# Sheet1.net
KiCad netlist of a schematic drawn in Altium Designer
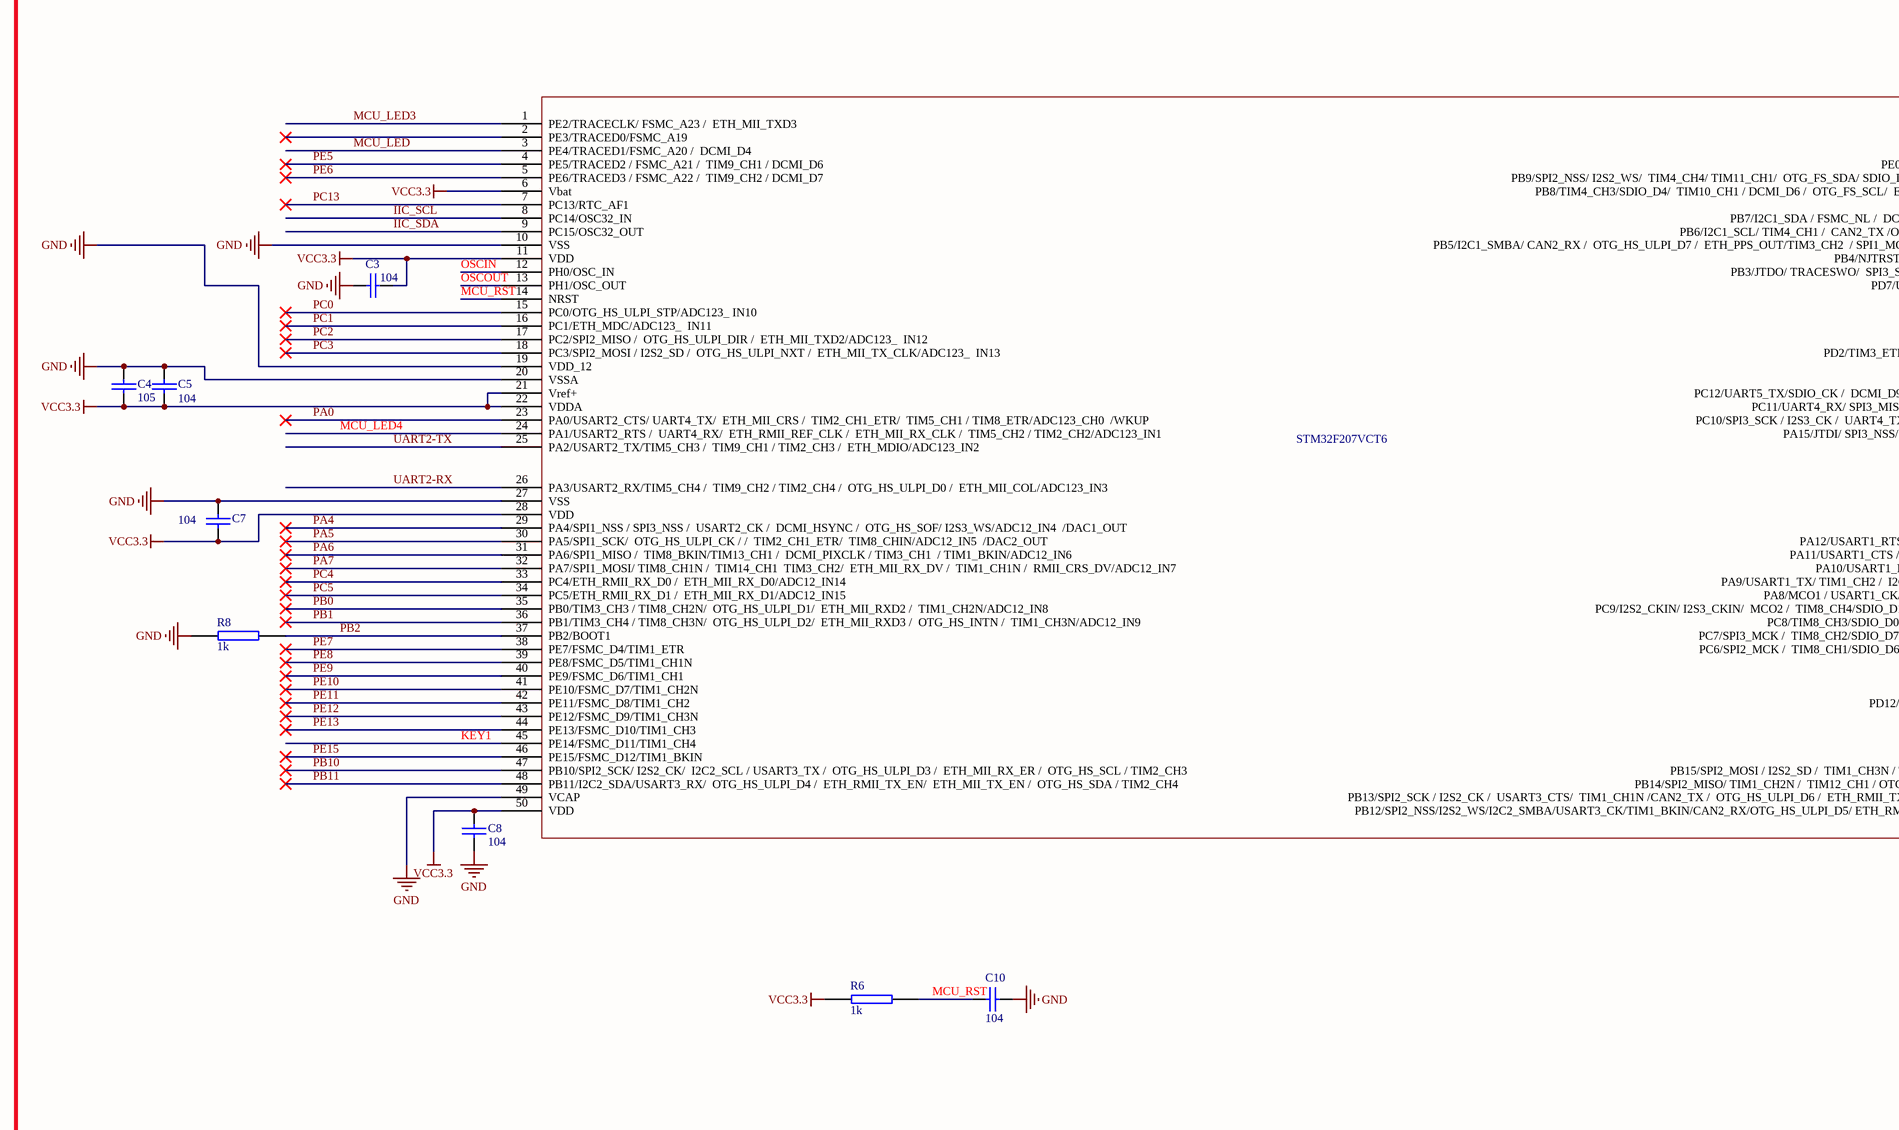
[diagram p0: Sheet1.SchDoc, top left]
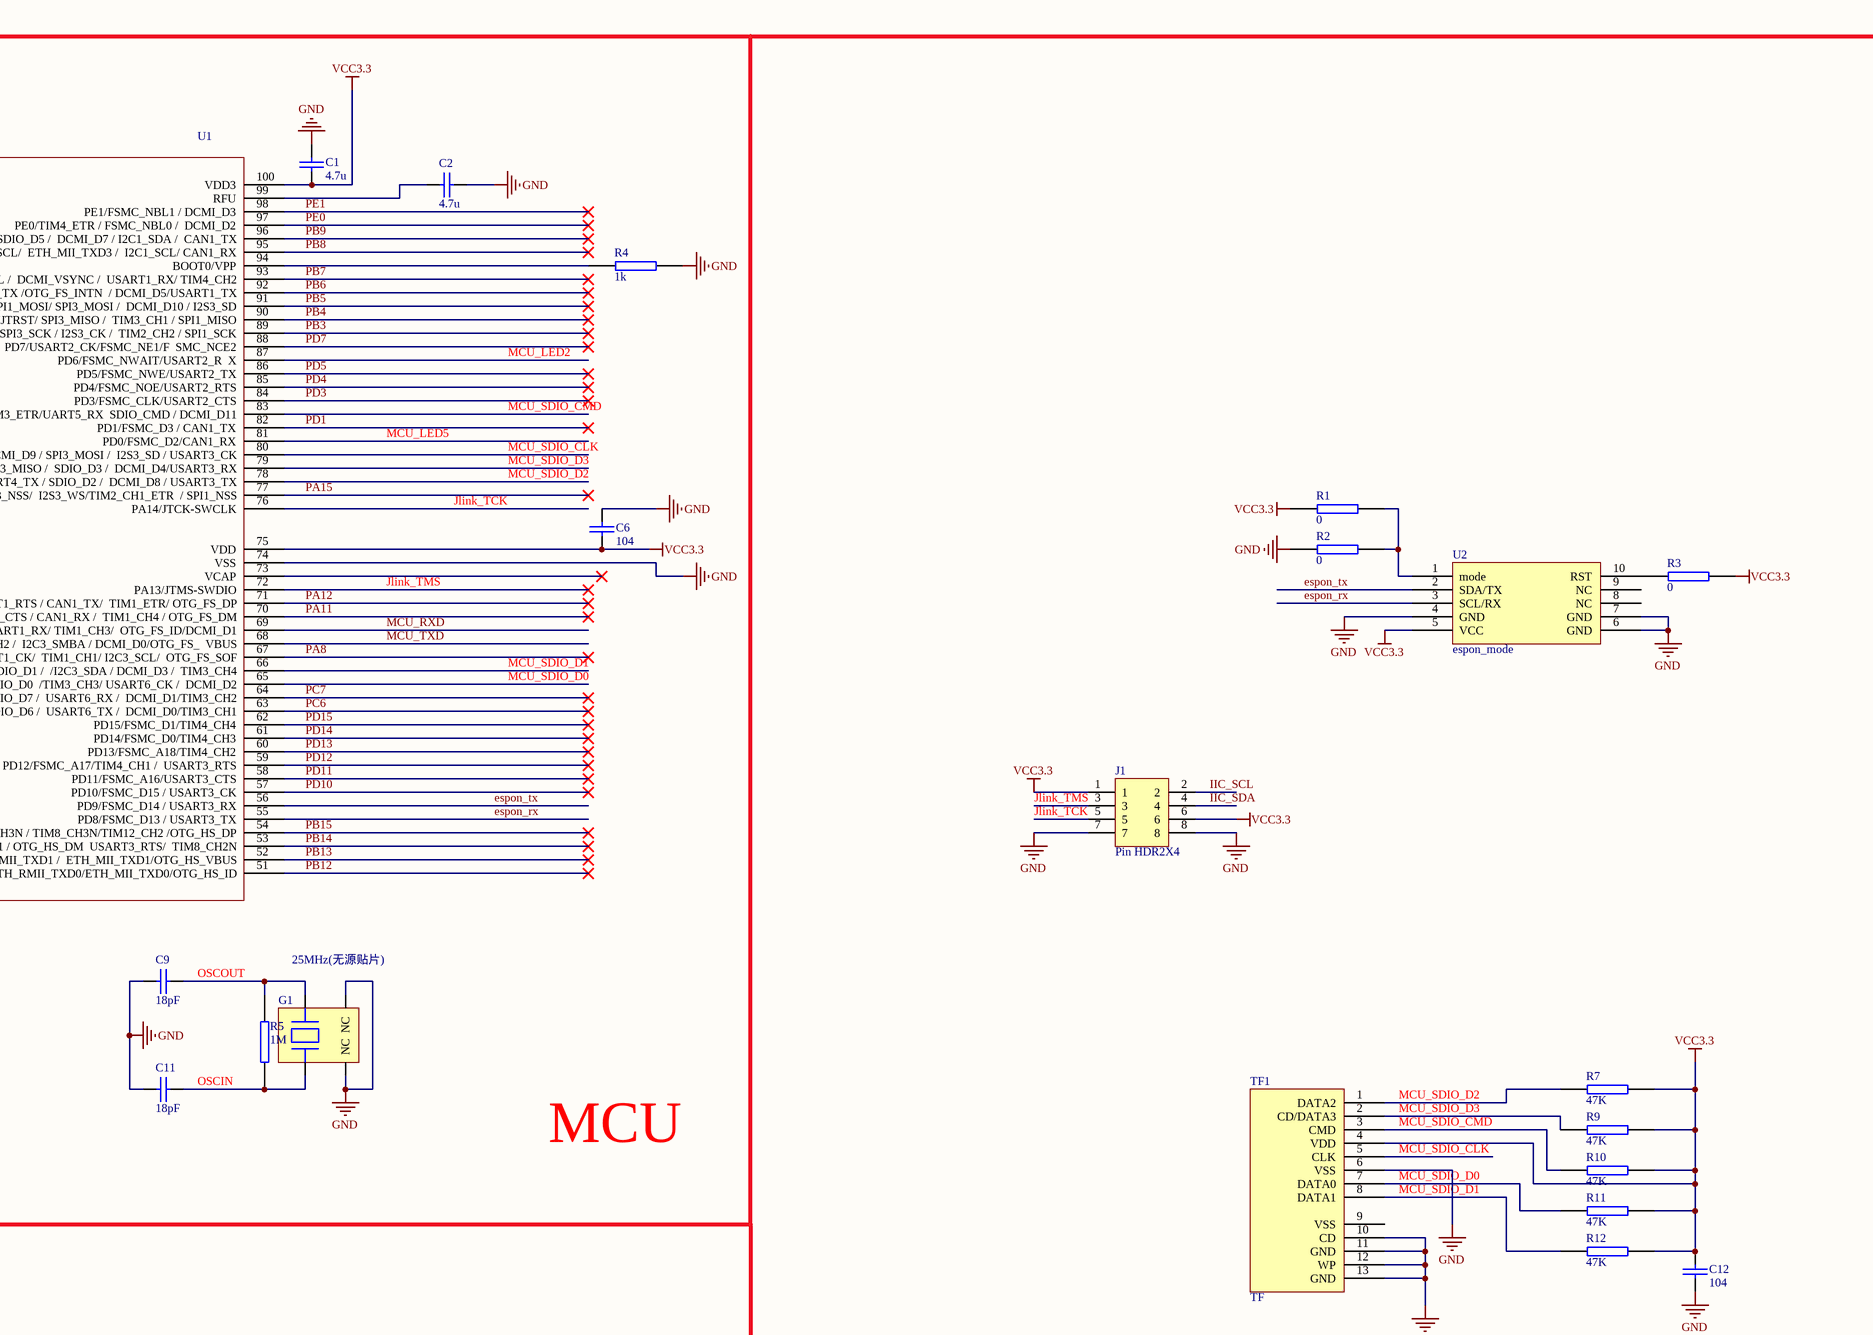
[diagram p1: Sheet1.SchDoc, top middle]
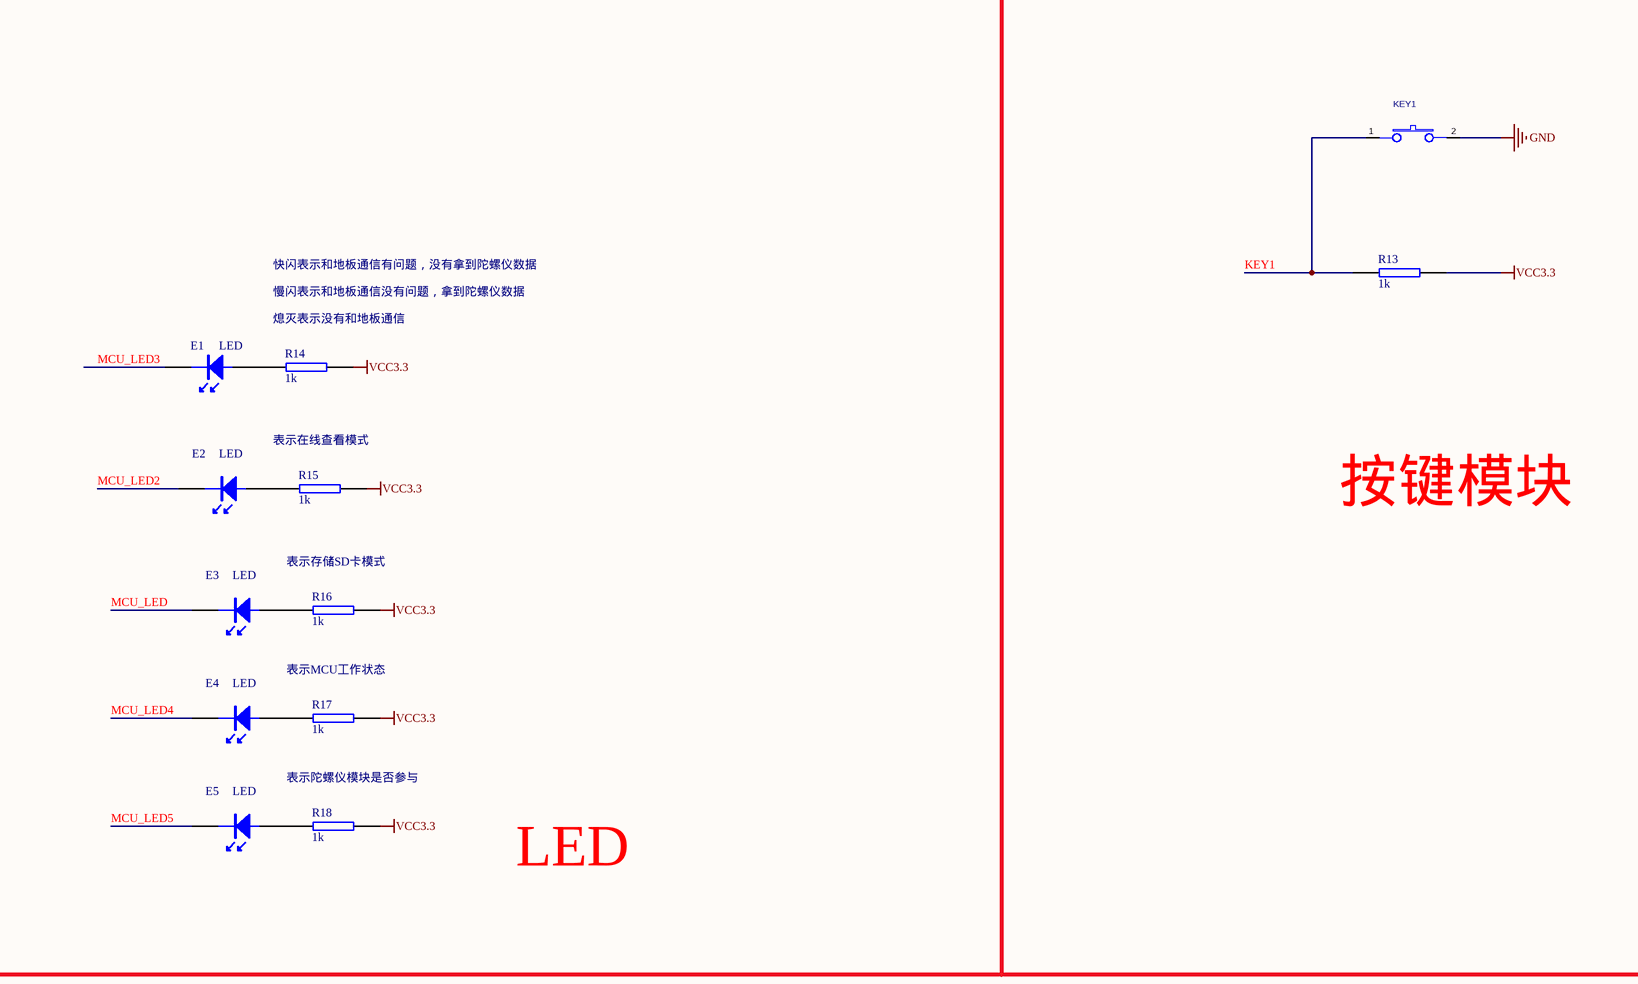
[diagram p2: Sheet1.SchDoc, bottom left]
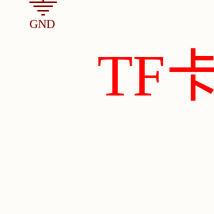
[diagram p3: Sheet1.SchDoc, bottom middle]
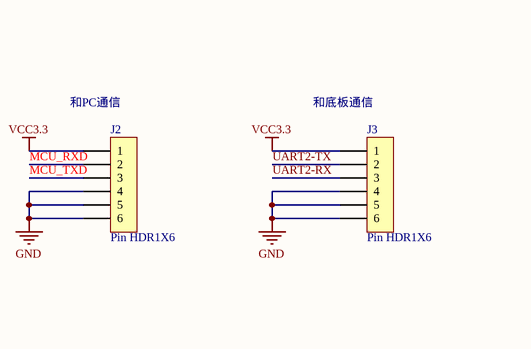
[diagram p4: Sheet1.SchDoc, bottom right]

(export (version "E")
  (design (tool "Eeschema 10.0.6"))
  (components
    (comp (ref "C1")
      (value "4.7u")
      (footprint "0603")
      (description "贴片电容")
      (libsource (lib "ZXBC") (part "CAP Nonpolarity"))
    )
    (comp (ref "C2")
      (value "4.7u")
      (footprint "0603")
      (description "贴片电容")
      (libsource (lib "ZXBC") (part "CAP Nonpolarity"))
    )
    (comp (ref "C3")
      (value "104")
      (footprint "0603")
      (description "贴片电容")
      (libsource (lib "ZXBC") (part "CAP Nonpolarity"))
    )
    (comp (ref "C4")
      (value "105")
      (footprint "0603")
      (description "贴片电容")
      (libsource (lib "ZXBC") (part "CAP Nonpolarity"))
    )
    (comp (ref "C5")
      (value "104")
      (footprint "0603")
      (description "贴片电容")
      (libsource (lib "ZXBC") (part "CAP Nonpolarity"))
    )
    (comp (ref "C6")
      (value "104")
      (footprint "0603")
      (description "贴片电容")
      (libsource (lib "ZXBC") (part "CAP Nonpolarity"))
    )
    (comp (ref "C7")
      (value "104")
      (footprint "0603")
      (description "贴片电容")
      (libsource (lib "ZXBC") (part "CAP Nonpolarity"))
    )
    (comp (ref "C8")
      (value "104")
      (footprint "0603")
      (description "贴片电容")
      (libsource (lib "ZXBC") (part "CAP Nonpolarity"))
    )
    (comp (ref "C9")
      (value "18pF")
      (footprint "0603")
      (description "无极电容")
      (libsource (lib "ZXBC") (part "CAP Nonpolarity"))
    )
    (comp (ref "C10")
      (value "104")
      (footprint "0603")
      (description "贴片电容")
      (libsource (lib "ZXBC") (part "CAP Nonpolarity"))
    )
    (comp (ref "C11")
      (value "18pF")
      (footprint "0603")
      (description "无极电容")
      (libsource (lib "ZXBC") (part "CAP Nonpolarity"))
    )
    (comp (ref "C12")
      (value "104")
      (footprint "0603")
      (description "无极电容")
      (libsource (lib "ZXBC") (part "CAP Nonpolarity"))
    )
    (comp (ref "E1")
      (value "LED")
      (footprint "LED_0603L")
      (description "LED灯")
      (libsource (lib "ZXBC") (part "LED"))
    )
    (comp (ref "E2")
      (value "LED")
      (footprint "LED_0603L")
      (description "LED灯")
      (libsource (lib "ZXBC") (part "LED"))
    )
    (comp (ref "E3")
      (value "LED")
      (footprint "LED_0603L")
      (description "LED灯")
      (libsource (lib "ZXBC") (part "LED"))
    )
    (comp (ref "E4")
      (value "LED")
      (footprint "LED_0603L")
      (description "LED灯")
      (libsource (lib "ZXBC") (part "LED"))
    )
    (comp (ref "E5")
      (value "LED")
      (footprint "LED_0603L")
      (description "LED灯")
      (libsource (lib "ZXBC") (part "LED"))
    )
    (comp (ref "G1")
      (value "25MHz(无源贴片)")
      (footprint "G3225")
      (description "无源晶振MCU使用")
      (libsource (lib "ZXBC") (part "MM-11B"))
    )
    (comp (ref "J1")
      (value "Pin HDR2X4")
      (footprint "PIN HDR2X4/2.54SMD")
      (libsource (lib "排针") (part "Pin HDR2X4"))
    )
    (comp (ref "J2")
      (value "Pin HDR1X6")
      (footprint "PIN GH1.25-4ping SMD")
      (libsource (lib "排针") (part "Pin HDR1X6"))
    )
    (comp (ref "J3")
      (value "Pin HDR1X6")
      (footprint "PIN GH1.25-4ping SMD")
      (libsource (lib "排针") (part "Pin HDR1X6"))
    )
    (comp (ref "KEY1")
      (value "H-3650AADW(NC)")
      (footprint "SW_PB_2P")
      (description "贴片按钮-2PIN(NC)")
      (fields (field (name "MANUFACTURER") "?"))
      (libsource (lib "chenjd") (part "SW_PB_2P"))
    )
    (comp (ref "R1") (value "0") (footprint "0603") (description "电阻") (libsource (lib "ZXBC") (part "R")))
    (comp (ref "R2") (value "0") (footprint "0603") (description "电阻") (libsource (lib "ZXBC") (part "R")))
    (comp (ref "R3") (value "0") (footprint "0603") (description "电阻") (libsource (lib "ZXBC") (part "R")))
    (comp (ref "R4") (value "1k") (footprint "0603") (description "电阻") (libsource (lib "ZXBC") (part "R")))
    (comp (ref "R5") (value "1M") (footprint "0603") (description "电阻") (libsource (lib "ZXBC") (part "R")))
    (comp (ref "R6") (value "1k") (footprint "0603") (description "电阻") (libsource (lib "ZXBC") (part "R")))
    (comp (ref "R7") (value "47K") (footprint "0603") (description "电阻") (libsource (lib "ZXBC") (part "R")))
    (comp (ref "R8") (value "1k") (footprint "0603") (description "电阻") (libsource (lib "ZXBC") (part "R")))
    (comp (ref "R9") (value "47K") (footprint "0603") (description "电阻") (libsource (lib "ZXBC") (part "R")))
    (comp (ref "R10") (value "47K") (footprint "0603") (description "电阻") (libsource (lib "ZXBC") (part "R")))
    (comp (ref "R11") (value "47K") (footprint "0603") (description "电阻") (libsource (lib "ZXBC") (part "R")))
    (comp (ref "R12") (value "47K") (footprint "0603") (description "电阻") (libsource (lib "ZXBC") (part "R")))
    (comp (ref "R13") (value "1k") (footprint "0603") (description "电阻") (libsource (lib "ZXBC") (part "R")))
    (comp (ref "R14") (value "1k") (footprint "0603") (description "电阻") (libsource (lib "ZXBC") (part "R")))
    (comp (ref "R15") (value "1k") (footprint "0603") (description "电阻") (libsource (lib "ZXBC") (part "R")))
    (comp (ref "R16") (value "1k") (footprint "0603") (description "电阻") (libsource (lib "ZXBC") (part "R")))
    (comp (ref "R17") (value "1k") (footprint "0603") (description "电阻") (libsource (lib "ZXBC") (part "R")))
    (comp (ref "R18") (value "1k") (footprint "0603") (description "电阻") (libsource (lib "ZXBC") (part "R")))
    (comp (ref "TF1") (value "TF") (footprint "TF") (description "TF卡") (libsource (lib "ZXBC") (part "TF")))
    (comp (ref "U1")
      (value "STM32F207VCT6")
      (footprint "LQFP-100")
      (libsource (lib "ZXBC") (part "STM32F207-1"))
    )
    (comp (ref "U2")
      (value "espon_mode")
      (footprint "espon_mode")
      (libsource (lib "chenjd") (part "espon_mode"))
    )
  )
  (nets
    (net (code "1") (name "/IIC_SCL") (class "Default")
      (node (ref "J1") (pin "2") (pinfunction "2_2") (pintype "passive"))
      (node (ref "U1") (pin "8") (pinfunction "PC14/OSC32_IN_8") (pintype "passive"))
    )
    (net (code "2") (name "/IIC_SDA") (class "Default")
      (node (ref "J1") (pin "4") (pinfunction "4_4") (pintype "passive"))
      (node (ref "U1") (pin "9") (pinfunction "PC15/OSC32_OUT_9") (pintype "passive"))
    )
    (net (code "3") (name "/Jlink_TCK") (class "Default")
      (node (ref "J1") (pin "5") (pinfunction "5_5") (pintype "passive"))
      (node (ref "U1") (pin "76") (pinfunction "PA14/JTCK-SWCLK_76") (pintype "passive"))
    )
    (net (code "4") (name "/Jlink_TMS") (class "Default")
      (node (ref "J1") (pin "3") (pinfunction "3_3") (pintype "passive"))
      (node (ref "U1") (pin "72") (pinfunction "PA13/JTMS-SWDIO_72") (pintype "passive"))
    )
    (net (code "5") (name "/KEY1") (class "Default")
      (node (ref "KEY1") (pin "1") (pinfunction "1_1") (pintype "passive"))
      (node (ref "R13") (pin "1") (pinfunction "1_1") (pintype "passive"))
      (node (ref "U1") (pin "45") (pinfunction "PE14/FSMC_D11/TIM1_CH4_45") (pintype "passive"))
    )
    (net (code "6") (name "/MCU_LED") (class "Default")
      (node (ref "E3") (pin "2") (pinfunction "2_2") (pintype "passive"))
      (node (ref "U1") (pin "3") (pinfunction "PE4/TRACED1/FSMC_A20_/__DCMI_D4_3") (pintype "passive"))
    )
    (net (code "7") (name "/MCU_LED2") (class "Default")
      (node (ref "E2") (pin "2") (pinfunction "2_2") (pintype "passive"))
      (node (ref "U1") (pin "87") (pinfunction "PD6/FSMC_NWAIT/USART2_R__X_87") (pintype "passive"))
    )
    (net (code "8") (name "/MCU_LED3") (class "Default")
      (node (ref "E1") (pin "2") (pinfunction "2_2") (pintype "passive"))
      (node (ref "U1") (pin "1") (pinfunction "PE2/TRACECLK/_FSMC_A23_/__ETH_MII_TXD3_1") (pintype "passive"))
    )
    (net (code "9") (name "/MCU_LED4") (class "Default")
      (node (ref "E4") (pin "2") (pinfunction "2_2") (pintype "passive"))
      (node (ref "U1") (pin "24") (pinfunction "PA1/USART2_RTS_/__UART4_RX/__ETH_RMII_REF_CLK_/__ETH_MII_RX_CLK_/__TIM5_CH2_/_TIM2_CH2/ADC123_IN1_24") (pintype "passive"))
    )
    (net (code "10") (name "/MCU_LED5") (class "Default")
      (node (ref "E5") (pin "2") (pinfunction "2_2") (pintype "passive"))
      (node (ref "U1") (pin "81") (pinfunction "PD0/FSMC_D2/CAN1_RX_81") (pintype "passive"))
    )
    (net (code "11") (name "/MCU_RST") (class "Default")
      (node (ref "C10") (pin "1") (pintype "passive"))
      (node (ref "R6") (pin "1") (pinfunction "1_1") (pintype "passive"))
      (node (ref "U1") (pin "14") (pinfunction "NRST_14") (pintype "passive"))
    )
    (net (code "12") (name "/MCU_RXD") (class "Default")
      (node (ref "J2") (pin "2") (pinfunction "2_2") (pintype "passive"))
      (node (ref "U1") (pin "69") (pinfunction "PA10/USART1_RX/_TIM1_CH3/__OTG_FS_ID/DCMI_D1_69") (pintype "passive"))
    )
    (net (code "13") (name "/MCU_SDIO_CLK") (class "Default")
      (node (ref "TF1") (pin "5") (pinfunction "CLK_5") (pintype "passive"))
      (node (ref "U1") (pin "80") (pinfunction "PC12/UART5_TX/SDIO_CK_/__DCMI_D9_/_SPI3_MOSI_/__I2S3_SD_/_USART3_CK_80") (pintype "passive"))
    )
    (net (code "14") (name "/MCU_SDIO_CMD") (class "Default")
      (node (ref "R10") (pin "1") (pinfunction "1_1") (pintype "passive"))
      (node (ref "TF1") (pin "3") (pinfunction "CMD_3") (pintype "passive"))
      (node (ref "U1") (pin "83") (pinfunction "PD2/TIM3_ETR/UART5_RX__SDIO_CMD_/_DCMI_D11_83") (pintype "passive"))
    )
    (net (code "15") (name "/MCU_SDIO_D0") (class "Default")
      (node (ref "R11") (pin "1") (pinfunction "1_1") (pintype "passive"))
      (node (ref "TF1") (pin "7") (pinfunction "DATA0_7") (pintype "passive"))
      (node (ref "U1") (pin "65") (pinfunction "PC8/TIM8_CH3/SDIO_D0__/TIM3_CH3/_USART6_CK_/__DCMI_D2_65") (pintype "passive"))
    )
    (net (code "16") (name "/MCU_SDIO_D1") (class "Default")
      (node (ref "R12") (pin "1") (pinfunction "1_1") (pintype "passive"))
      (node (ref "TF1") (pin "8") (pinfunction "DATA1_8") (pintype "passive"))
      (node (ref "U1") (pin "66") (pinfunction "PC9/I2S2_CKIN/_I2S3_CKIN/__MCO2_/__TIM8_CH4/SDIO_D1_/__/I2C3_SDA_/_DCMI_D3_/__TIM3_CH4_66") (pintype "passive"))
    )
    (net (code "17") (name "/MCU_SDIO_D2") (class "Default")
      (node (ref "R7") (pin "1") (pinfunction "1_1") (pintype "passive"))
      (node (ref "TF1") (pin "1") (pinfunction "DATA2_1") (pintype "passive"))
      (node (ref "U1") (pin "78") (pinfunction "PC10/SPI3_SCK_/_I2S3_CK_/__UART4_TX_/_SDIO_D2_/__DCMI_D8_/_USART3_TX_78") (pintype "passive"))
    )
    (net (code "18") (name "/MCU_SDIO_D3") (class "Default")
      (node (ref "R9") (pin "1") (pinfunction "1_1") (pintype "passive"))
      (node (ref "TF1") (pin "2") (pinfunction "CD/DATA3_2") (pintype "passive"))
      (node (ref "U1") (pin "79") (pinfunction "PC11/UART4_RX/_SPI3_MISO_/__SDIO_D3_/__DCMI_D4/USART3_RX_79") (pintype "passive"))
    )
    (net (code "19") (name "/MCU_TXD") (class "Default")
      (node (ref "J2") (pin "3") (pinfunction "3_3") (pintype "passive"))
      (node (ref "U1") (pin "68") (pinfunction "PA9/USART1_TX/_TIM1_CH2_/__I2C3_SMBA_/_DCMI_D0/OTG_FS___VBUS_68") (pintype "passive"))
    )
    (net (code "20") (name "/OSCIN") (class "Default")
      (node (ref "C11") (pin "2") (pintype "passive"))
      (node (ref "G1") (pin "1") (pinfunction "1_1") (pintype "passive"))
      (node (ref "R5") (pin "2") (pinfunction "2_2") (pintype "passive"))
      (node (ref "U1") (pin "12") (pinfunction "PH0/OSC_IN_12") (pintype "passive"))
    )
    (net (code "21") (name "/OSCOUT") (class "Default")
      (node (ref "C9") (pin "2") (pintype "passive"))
      (node (ref "G1") (pin "3") (pinfunction "3_3") (pintype "passive"))
      (node (ref "R5") (pin "1") (pinfunction "1_1") (pintype "passive"))
      (node (ref "U1") (pin "13") (pinfunction "PH1/OSC_OUT_13") (pintype "passive"))
    )
    (net (code "22") (name "/PA0") (class "Default")
      (node (ref "U1") (pin "23") (pinfunction "PA0/USART2_CTS/_UART4_TX/__ETH_MII_CRS_/__TIM2_CH1_ETR/__TIM5_CH1_/_TIM8_ETR/ADC123_CH0__/WKUP_23") (pintype "passive+no_connect"))
    )
    (net (code "23") (name "/PA4") (class "Default")
      (node (ref "U1") (pin "29") (pinfunction "PA4/SPI1_NSS_/_SPI3_NSS_/__USART2_CK_/__DCMI_HSYNC_/__OTG_HS_SOF/_I2S3_WS/ADC12_IN4__/DAC1_OUT_29") (pintype "passive+no_connect"))
    )
    (net (code "24") (name "/PA5") (class "Default")
      (node (ref "U1") (pin "30") (pinfunction "PA5/SPI1_SCK/__OTG_HS_ULPI_CK_/_/__TIM2_CH1_ETR/__TIM8_CHIN/ADC12_IN5__/DAC2_OUT_30") (pintype "passive+no_connect"))
    )
    (net (code "25") (name "/PA6") (class "Default")
      (node (ref "U1") (pin "31") (pinfunction "PA6/SPI1_MISO_/__TIM8_BKIN/TIM13_CH1_/__DCMI_PIXCLK_/_TIM3_CH1__/_TIM1_BKIN/ADC12_IN6_31") (pintype "passive+no_connect"))
    )
    (net (code "26") (name "/PA7") (class "Default")
      (node (ref "U1") (pin "32") (pinfunction "PA7/SPI1_MOSI/_TIM8_CH1N_/__TIM14_CH1__TIM3_CH2/__ETH_MII_RX_DV_/__TIM1_CH1N_/__RMII_CRS_DV/ADC12_IN7_32") (pintype "passive+no_connect"))
    )
    (net (code "27") (name "/PA8") (class "Default")
      (node (ref "U1") (pin "67") (pinfunction "PA8/MCO1_/_USART1_CK/__TIM1_CH1/_I2C3_SCL/__OTG_FS_SOF_67") (pintype "passive+no_connect"))
    )
    (net (code "28") (name "/PA11") (class "Default")
      (node (ref "U1") (pin "70") (pinfunction "PA11/USART1_CTS_/_CAN1_RX_/__TIM1_CH4_/_OTG_FS_DM_70") (pintype "passive+no_connect"))
    )
    (net (code "29") (name "/PA12") (class "Default")
      (node (ref "U1") (pin "71") (pinfunction "PA12/USART1_RTS_/_CAN1_TX/__TIM1_ETR/_OTG_FS_DP_71") (pintype "passive+no_connect"))
    )
    (net (code "30") (name "/PA15") (class "Default")
      (node (ref "U1") (pin "77") (pinfunction "PA15/JTDI/_SPI3_NSS/__I2S3_WS/TIM2_CH1_ETR__/_SPI1_NSS_77") (pintype "passive+no_connect"))
    )
    (net (code "31") (name "/PB0") (class "Default")
      (node (ref "U1") (pin "35") (pinfunction "PB0/TIM3_CH3_/_TIM8_CH2N/__OTG_HS_ULPI_D1/__ETH_MII_RXD2_/__TIM1_CH2N/ADC12_IN8_35") (pintype "passive+no_connect"))
    )
    (net (code "32") (name "/PB1") (class "Default")
      (node (ref "U1") (pin "36") (pinfunction "PB1/TIM3_CH4_/_TIM8_CH3N/__OTG_HS_ULPI_D2/__ETH_MII_RXD3_/__OTG_HS_INTN_/__TIM1_CH3N/ADC12_IN9_36") (pintype "passive+no_connect"))
    )
    (net (code "33") (name "/PB2") (class "Default")
      (node (ref "R8") (pin "2") (pinfunction "2_2") (pintype "passive"))
      (node (ref "U1") (pin "37") (pinfunction "PB2/BOOT1_37") (pintype "passive"))
    )
    (net (code "34") (name "/PB3") (class "Default")
      (node (ref "U1") (pin "89") (pinfunction "PB3/JTDO/_TRACESWO/__SPI3_SCK_/_I2S3_CK_/__TIM2_CH2_/_SPI1_SCK_89") (pintype "passive+no_connect"))
    )
    (net (code "35") (name "/PB4") (class "Default")
      (node (ref "U1") (pin "90") (pinfunction "PB4/NJTRST/_SPI3_MISO_/__TIM3_CH1_/_SPI1_MISO_90") (pintype "passive+no_connect"))
    )
    (net (code "36") (name "/PB5") (class "Default")
      (node (ref "U1") (pin "91") (pinfunction "PB5/I2C1_SMBA/_CAN2_RX_/__OTG_HS_ULPI_D7_/__ETH_PPS_OUT/TIM3_CH2__/_SPI1_MOSI/_SPI3_MOSI_/__DCMI_D10_/_I2S3_SD_91") (pintype "passive+no_connect"))
    )
    (net (code "37") (name "/PB6") (class "Default")
      (node (ref "U1") (pin "92") (pinfunction "PB6/I2C1_SCL/_TIM4_CH1_/__CAN2_TX_/OTG_FS_INTN__/_DCMI_D5/USART1_TX_92") (pintype "passive+no_connect"))
    )
    (net (code "38") (name "/PB7") (class "Default")
      (node (ref "U1") (pin "93") (pinfunction "PB7/I2C1_SDA_/_FSMC_NL_/__DCMI_VSYNC_/__USART1_RX/_TIM4_CH2_93") (pintype "passive+no_connect"))
    )
    (net (code "39") (name "/PB8") (class "Default")
      (node (ref "U1") (pin "95") (pinfunction "PB8/TIM4_CH3/SDIO_D4/__TIM10_CH1_/_DCMI_D6_/__OTG_FS_SCL/__ETH_MII_TXD3_/__I2C1_SCL/_CAN1_RX_95") (pintype "passive+no_connect"))
    )
    (net (code "40") (name "/PB9") (class "Default")
      (node (ref "U1") (pin "96") (pinfunction "PB9/SPI2_NSS/_I2S2_WS/__TIM4_CH4/_TIM11_CH1/__OTG_FS_SDA/_SDIO_D5_/__DCMI_D7_/_I2C1_SDA_/__CAN1_TX_96") (pintype "passive+no_connect"))
    )
    (net (code "41") (name "/PB10") (class "Default")
      (node (ref "U1") (pin "47") (pinfunction "PB10/SPI2_SCK/_I2S2_CK/__I2C2_SCL_/_USART3_TX_/__OTG_HS_ULPI_D3_/__ETH_MII_RX_ER_/__OTG_HS_SCL_/_TIM2_CH3_47") (pintype "passive+no_connect"))
    )
    (net (code "42") (name "/PB11") (class "Default")
      (node (ref "U1") (pin "48") (pinfunction "PB11/I2C2_SDA/USART3_RX/__OTG_HS_ULPI_D4_/__ETH_RMII_TX_EN/__ETH_MII_TX_EN_/__OTG_HS_SDA_/_TIM2_CH4_48") (pintype "passive+no_connect"))
    )
    (net (code "43") (name "/PB12") (class "Default")
      (node (ref "U1") (pin "51") (pinfunction "PB12/SPI2_NSS/I2S2_WS/I2C2_SMBA/USART3_CK/TIM1_BKIN/CAN2_RX/OTG_HS_ULPI_D5/_ETH_RMII_TXD0/ETH_MII_TXD0/OTG_HS_ID_51") (pintype "passive+no_connect"))
    )
    (net (code "44") (name "/PB13") (class "Default")
      (node (ref "U1") (pin "52") (pinfunction "PB13/SPI2_SCK_/_I2S2_CK_/__USART3_CTS/__TIM1_CH1N_/CAN2_TX_/__OTG_HS_ULPI_D6_/__ETH_RMII_TXD1_/__ETH_MII_TXD1/OTG_HS_VBUS_52") (pintype "passive+no_connect"))
    )
    (net (code "45") (name "/PB14") (class "Default")
      (node (ref "U1") (pin "53") (pinfunction "PB14/SPI2_MISO/_TIM1_CH2N_/__TIM12_CH1_/_OTG_HS_DM__USART3_RTS/__TIM8_CH2N_53") (pintype "passive+no_connect"))
    )
    (net (code "46") (name "/PB15") (class "Default")
      (node (ref "U1") (pin "54") (pinfunction "PB15/SPI2_MOSI_/_I2S2_SD_/__TIM1_CH3N_/_TIM8_CH3N/TIM12_CH2_/OTG_HS_DP_54") (pintype "passive+no_connect"))
    )
    (net (code "47") (name "/PC0") (class "Default")
      (node (ref "U1") (pin "15") (pinfunction "PC0/OTG_HS_ULPI_STP/ADC123__IN10_15") (pintype "passive+no_connect"))
    )
    (net (code "48") (name "/PC1") (class "Default")
      (node (ref "U1") (pin "16") (pinfunction "PC1/ETH_MDC/ADC123___IN11_16") (pintype "passive+no_connect"))
    )
    (net (code "49") (name "/PC2") (class "Default")
      (node (ref "U1") (pin "17") (pinfunction "PC2/SPI2_MISO_/__OTG_HS_ULPI_DIR_/__ETH_MII_TXD2/ADC123___IN12_17") (pintype "passive+no_connect"))
    )
    (net (code "50") (name "/PC3") (class "Default")
      (node (ref "U1") (pin "18") (pinfunction "PC3/SPI2_MOSI_/_I2S2_SD_/__OTG_HS_ULPI_NXT_/__ETH_MII_TX_CLK/ADC123___IN13_18") (pintype "passive+no_connect"))
    )
    (net (code "51") (name "/PC4") (class "Default")
      (node (ref "U1") (pin "33") (pinfunction "PC4/ETH_RMII_RX_D0_/__ETH_MII_RX_D0/ADC12_IN14_33") (pintype "passive+no_connect"))
    )
    (net (code "52") (name "/PC5") (class "Default")
      (node (ref "U1") (pin "34") (pinfunction "PC5/ETH_RMII_RX_D1_/__ETH_MII_RX_D1/ADC12_IN15_34") (pintype "passive+no_connect"))
    )
    (net (code "53") (name "/PC6") (class "Default")
      (node (ref "U1") (pin "63") (pinfunction "PC6/SPI2_MCK_/__TIM8_CH1/SDIO_D6_/__USART6_TX_/__DCMI_D0/TIM3_CH1_63") (pintype "passive+no_connect"))
    )
    (net (code "54") (name "/PC7") (class "Default")
      (node (ref "U1") (pin "64") (pinfunction "PC7/SPI3_MCK_/__TIM8_CH2/SDIO_D7_/__USART6_RX_/__DCMI_D1/TIM3_CH2_64") (pintype "passive+no_connect"))
    )
    (net (code "55") (name "/PC13") (class "Default")
      (node (ref "U1") (pin "7") (pinfunction "PC13/RTC_AF1_7") (pintype "passive+no_connect"))
    )
    (net (code "56") (name "/PD1") (class "Default")
      (node (ref "U1") (pin "82") (pinfunction "PD1/FSMC_D3_/_CAN1_TX_82") (pintype "passive+no_connect"))
    )
    (net (code "57") (name "/PD3") (class "Default")
      (node (ref "U1") (pin "84") (pinfunction "PD3/FSMC_CLK/USART2_CTS_84") (pintype "passive+no_connect"))
    )
    (net (code "58") (name "/PD4") (class "Default")
      (node (ref "U1") (pin "85") (pinfunction "PD4/FSMC_NOE/USART2_RTS_85") (pintype "passive+no_connect"))
    )
    (net (code "59") (name "/PD5") (class "Default")
      (node (ref "U1") (pin "86") (pinfunction "PD5/FSMC_NWE/USART2_TX_86") (pintype "passive+no_connect"))
    )
    (net (code "60") (name "/PD7") (class "Default")
      (node (ref "U1") (pin "88") (pinfunction "PD7/USART2_CK/FSMC_NE1/F__SMC_NCE2_88") (pintype "passive+no_connect"))
    )
    (net (code "61") (name "/PD10") (class "Default")
      (node (ref "U1") (pin "57") (pinfunction "PD10/FSMC_D15_/_USART3_CK_57") (pintype "passive+no_connect"))
    )
    (net (code "62") (name "/PD11") (class "Default")
      (node (ref "U1") (pin "58") (pinfunction "PD11/FSMC_A16/USART3_CTS_58") (pintype "passive+no_connect"))
    )
    (net (code "63") (name "/PD12") (class "Default")
      (node (ref "U1") (pin "59") (pinfunction "PD12/FSMC_A17/TIM4_CH1_/__USART3_RTS_59") (pintype "passive+no_connect"))
    )
    (net (code "64") (name "/PD13") (class "Default")
      (node (ref "U1") (pin "60") (pinfunction "PD13/FSMC_A18/TIM4_CH2_60") (pintype "passive+no_connect"))
    )
    (net (code "65") (name "/PD14") (class "Default")
      (node (ref "U1") (pin "61") (pinfunction "PD14/FSMC_D0/TIM4_CH3_61") (pintype "passive+no_connect"))
    )
    (net (code "66") (name "/PD15") (class "Default")
      (node (ref "U1") (pin "62") (pinfunction "PD15/FSMC_D1/TIM4_CH4_62") (pintype "passive+no_connect"))
    )
    (net (code "67") (name "/PE0") (class "Default")
      (node (ref "U1") (pin "97") (pinfunction "PE0/TIM4_ETR_/_FSMC_NBL0_/__DCMI_D2_97") (pintype "passive+no_connect"))
    )
    (net (code "68") (name "/PE1") (class "Default")
      (node (ref "U1") (pin "98") (pinfunction "PE1/FSMC_NBL1_/_DCMI_D3_98") (pintype "passive+no_connect"))
    )
    (net (code "69") (name "/PE5") (class "Default")
      (node (ref "U1") (pin "4") (pinfunction "PE5/TRACED2_/_FSMC_A21_/__TIM9_CH1_/_DCMI_D6_4") (pintype "passive+no_connect"))
    )
    (net (code "70") (name "/PE6") (class "Default")
      (node (ref "U1") (pin "5") (pinfunction "PE6/TRACED3_/_FSMC_A22_/__TIM9_CH2_/_DCMI_D7_5") (pintype "passive+no_connect"))
    )
    (net (code "71") (name "/PE7") (class "Default")
      (node (ref "U1") (pin "38") (pinfunction "PE7/FSMC_D4/TIM1_ETR_38") (pintype "passive+no_connect"))
    )
    (net (code "72") (name "/PE8") (class "Default")
      (node (ref "U1") (pin "39") (pinfunction "PE8/FSMC_D5/TIM1_CH1N_39") (pintype "passive+no_connect"))
    )
    (net (code "73") (name "/PE9") (class "Default")
      (node (ref "U1") (pin "40") (pinfunction "PE9/FSMC_D6/TIM1_CH1_40") (pintype "passive+no_connect"))
    )
    (net (code "74") (name "/PE10") (class "Default")
      (node (ref "U1") (pin "41") (pinfunction "PE10/FSMC_D7/TIM1_CH2N_41") (pintype "passive+no_connect"))
    )
    (net (code "75") (name "/PE11") (class "Default")
      (node (ref "U1") (pin "42") (pinfunction "PE11/FSMC_D8/TIM1_CH2_42") (pintype "passive+no_connect"))
    )
    (net (code "76") (name "/PE12") (class "Default")
      (node (ref "U1") (pin "43") (pinfunction "PE12/FSMC_D9/TIM1_CH3N_43") (pintype "passive+no_connect"))
    )
    (net (code "77") (name "/PE13") (class "Default")
      (node (ref "U1") (pin "44") (pinfunction "PE13/FSMC_D10/TIM1_CH3_44") (pintype "passive+no_connect"))
    )
    (net (code "78") (name "/PE15") (class "Default")
      (node (ref "U1") (pin "46") (pinfunction "PE15/FSMC_D12/TIM1_BKIN_46") (pintype "passive+no_connect"))
    )
    (net (code "79") (name "/UART2-RX") (class "Default")
      (node (ref "J3") (pin "3") (pinfunction "3_3") (pintype "passive"))
      (node (ref "U1") (pin "26") (pinfunction "PA3/USART2_RX/TIM5_CH4_/__TIM9_CH2_/_TIM2_CH4_/__OTG_HS_ULPI_D0_/__ETH_MII_COL/ADC123_IN3_26") (pintype "passive"))
    )
    (net (code "80") (name "/UART2-TX") (class "Default")
      (node (ref "J3") (pin "2") (pinfunction "2_2") (pintype "passive"))
      (node (ref "U1") (pin "25") (pinfunction "PA2/USART2_TX/TIM5_CH3_/__TIM9_CH1_/_TIM2_CH3_/__ETH_MDIO/ADC123_IN2_25") (pintype "passive"))
    )
    (net (code "81") (name "/espon_rx") (class "Default")
      (node (ref "U1") (pin "55") (pinfunction "PD8/FSMC_D13_/_USART3_TX_55") (pintype "passive"))
      (node (ref "U2") (pin "3") (pinfunction "SCL/RX_3") (pintype "passive"))
    )
    (net (code "82") (name "/espon_tx") (class "Default")
      (node (ref "U1") (pin "56") (pinfunction "PD9/FSMC_D14_/_USART3_RX_56") (pintype "passive"))
      (node (ref "U2") (pin "2") (pinfunction "SDA/TX_2") (pintype "passive"))
    )
    (net (code "83") (name "GND") (class "Default")
      (node (ref "C1") (pin "2") (pintype "passive"))
      (node (ref "C10") (pin "2") (pintype "passive"))
      (node (ref "C11") (pin "1") (pintype "passive"))
      (node (ref "C12") (pin "2") (pintype "passive"))
      (node (ref "C2") (pin "1") (pintype "passive"))
      (node (ref "C3") (pin "1") (pintype "passive"))
      (node (ref "C4") (pin "2") (pintype "passive"))
      (node (ref "C5") (pin "2") (pintype "passive"))
      (node (ref "C6") (pin "2") (pintype "passive"))
      (node (ref "C7") (pin "2") (pintype "passive"))
      (node (ref "C8") (pin "2") (pintype "passive"))
      (node (ref "C9") (pin "1") (pintype "passive"))
      (node (ref "G1") (pin "2") (pinfunction "NC_2") (pintype "passive"))
      (node (ref "G1") (pin "4") (pinfunction "NC_4") (pintype "passive"))
      (node (ref "J1") (pin "7") (pinfunction "7_7") (pintype "passive"))
      (node (ref "J1") (pin "8") (pinfunction "8_8") (pintype "passive"))
      (node (ref "J2") (pin "4") (pinfunction "4_4") (pintype "passive"))
      (node (ref "J2") (pin "5") (pinfunction "5_5") (pintype "passive"))
      (node (ref "J2") (pin "6") (pinfunction "6_6") (pintype "passive"))
      (node (ref "J3") (pin "4") (pinfunction "4_4") (pintype "passive"))
      (node (ref "J3") (pin "5") (pinfunction "5_5") (pintype "passive"))
      (node (ref "J3") (pin "6") (pinfunction "6_6") (pintype "passive"))
      (node (ref "KEY1") (pin "2") (pinfunction "2_2") (pintype "passive"))
      (node (ref "R2") (pin "1") (pinfunction "1_1") (pintype "passive"))
      (node (ref "R4") (pin "1") (pinfunction "1_1") (pintype "passive"))
      (node (ref "R8") (pin "1") (pinfunction "1_1") (pintype "passive"))
      (node (ref "TF1") (pin "10") (pinfunction "CD_10") (pintype "passive"))
      (node (ref "TF1") (pin "11") (pinfunction "GND_11") (pintype "passive"))
      (node (ref "TF1") (pin "12") (pinfunction "WP_12") (pintype "passive"))
      (node (ref "TF1") (pin "13") (pinfunction "GND_13") (pintype "passive"))
      (node (ref "TF1") (pin "6") (pinfunction "VSS_6") (pintype "passive"))
      (node (ref "U1") (pin "10") (pinfunction "VSS_10") (pintype "passive"))
      (node (ref "U1") (pin "19") (pinfunction "VDD_12_19") (pintype "passive"))
      (node (ref "U1") (pin "20") (pinfunction "VSSA_20") (pintype "passive"))
      (node (ref "U1") (pin "27") (pinfunction "VSS_27") (pintype "passive"))
      (node (ref "U1") (pin "49") (pinfunction "VCAP_49") (pintype "passive"))
      (node (ref "U1") (pin "74") (pinfunction "VSS_74") (pintype "passive"))
      (node (ref "U2") (pin "4") (pinfunction "GND_4") (pintype "passive"))
      (node (ref "U2") (pin "6") (pinfunction "GND_6") (pintype "passive"))
      (node (ref "U2") (pin "7") (pinfunction "GND_7") (pintype "passive"))
    )
    (net (code "84") (name "Net-(E1-Pad1)") (class "Default")
      (node (ref "E1") (pin "1") (pinfunction "1_1") (pintype "passive"))
      (node (ref "R14") (pin "1") (pinfunction "1_1") (pintype "passive"))
    )
    (net (code "85") (name "Net-(E2-Pad1)") (class "Default")
      (node (ref "E2") (pin "1") (pinfunction "1_1") (pintype "passive"))
      (node (ref "R15") (pin "1") (pinfunction "1_1") (pintype "passive"))
    )
    (net (code "86") (name "Net-(E3-Pad1)") (class "Default")
      (node (ref "E3") (pin "1") (pinfunction "1_1") (pintype "passive"))
      (node (ref "R16") (pin "1") (pinfunction "1_1") (pintype "passive"))
    )
    (net (code "87") (name "Net-(E4-Pad1)") (class "Default")
      (node (ref "E4") (pin "1") (pinfunction "1_1") (pintype "passive"))
      (node (ref "R17") (pin "1") (pinfunction "1_1") (pintype "passive"))
    )
    (net (code "88") (name "Net-(E5-Pad1)") (class "Default")
      (node (ref "E5") (pin "1") (pinfunction "1_1") (pintype "passive"))
      (node (ref "R18") (pin "1") (pinfunction "1_1") (pintype "passive"))
    )
    (net (code "89") (name "Net-(U1-BOOT0{slash}VPP)") (class "Default")
      (node (ref "R4") (pin "2") (pinfunction "2_2") (pintype "passive"))
      (node (ref "U1") (pin "94") (pinfunction "BOOT0/VPP_94") (pintype "passive"))
    )
    (net (code "90") (name "Net-(U1-RFU)") (class "Default")
      (node (ref "C2") (pin "2") (pintype "passive"))
      (node (ref "U1") (pin "99") (pinfunction "RFU_99") (pintype "passive"))
    )
    (net (code "91") (name "Net-(U2-RST)") (class "Default")
      (node (ref "R3") (pin "1") (pinfunction "1_1") (pintype "passive"))
      (node (ref "U2") (pin "10") (pinfunction "RST_10") (pintype "passive"))
    )
    (net (code "92") (name "Net-(U2-mode)") (class "Default")
      (node (ref "R1") (pin "2") (pinfunction "2_2") (pintype "passive"))
      (node (ref "R2") (pin "2") (pinfunction "2_2") (pintype "passive"))
      (node (ref "U2") (pin "1") (pinfunction "mode_1") (pintype "passive"))
    )
    (net (code "93") (name "VCC3.3") (class "Default")
      (node (ref "C1") (pin "1") (pintype "passive"))
      (node (ref "C12") (pin "1") (pintype "passive"))
      (node (ref "C3") (pin "2") (pintype "passive"))
      (node (ref "C4") (pin "1") (pintype "passive"))
      (node (ref "C5") (pin "1") (pintype "passive"))
      (node (ref "C6") (pin "1") (pintype "passive"))
      (node (ref "C7") (pin "1") (pintype "passive"))
      (node (ref "C8") (pin "1") (pintype "passive"))
      (node (ref "J1") (pin "1") (pinfunction "1_1") (pintype "passive"))
      (node (ref "J1") (pin "6") (pinfunction "6_6") (pintype "passive"))
      (node (ref "J2") (pin "1") (pinfunction "1_1") (pintype "passive"))
      (node (ref "J3") (pin "1") (pinfunction "1_1") (pintype "passive"))
      (node (ref "R1") (pin "1") (pinfunction "1_1") (pintype "passive"))
      (node (ref "R10") (pin "2") (pinfunction "2_2") (pintype "passive"))
      (node (ref "R11") (pin "2") (pinfunction "2_2") (pintype "passive"))
      (node (ref "R12") (pin "2") (pinfunction "2_2") (pintype "passive"))
      (node (ref "R13") (pin "2") (pinfunction "2_2") (pintype "passive"))
      (node (ref "R14") (pin "2") (pinfunction "2_2") (pintype "passive"))
      (node (ref "R15") (pin "2") (pinfunction "2_2") (pintype "passive"))
      (node (ref "R16") (pin "2") (pinfunction "2_2") (pintype "passive"))
      (node (ref "R17") (pin "2") (pinfunction "2_2") (pintype "passive"))
      (node (ref "R18") (pin "2") (pinfunction "2_2") (pintype "passive"))
      (node (ref "R3") (pin "2") (pinfunction "2_2") (pintype "passive"))
      (node (ref "R6") (pin "2") (pinfunction "2_2") (pintype "passive"))
      (node (ref "R7") (pin "2") (pinfunction "2_2") (pintype "passive"))
      (node (ref "R9") (pin "2") (pinfunction "2_2") (pintype "passive"))
      (node (ref "TF1") (pin "4") (pinfunction "VDD_4") (pintype "passive"))
      (node (ref "U1") (pin "100") (pinfunction "VDD3_100") (pintype "passive"))
      (node (ref "U1") (pin "11") (pinfunction "VDD_11") (pintype "passive"))
      (node (ref "U1") (pin "21") (pinfunction "Vref+_21") (pintype "passive"))
      (node (ref "U1") (pin "22") (pinfunction "VDDA_22") (pintype "passive"))
      (node (ref "U1") (pin "28") (pinfunction "VDD_28") (pintype "passive"))
      (node (ref "U1") (pin "50") (pinfunction "VDD_50") (pintype "passive"))
      (node (ref "U1") (pin "6") (pinfunction "Vbat_6") (pintype "passive"))
      (node (ref "U1") (pin "75") (pinfunction "VDD_75") (pintype "passive"))
      (node (ref "U2") (pin "5") (pinfunction "VCC_5") (pintype "passive"))
    )
    (net (code "94") (name "unconnected-(TF1-VSS-Pad9)") (class "Default")
      (node (ref "TF1") (pin "9") (pinfunction "VSS_9") (pintype "passive"))
    )
    (net (code "95") (name "unconnected-(U1-PE3{slash}TRACED0{slash}FSMC_A19-Pad2)") (class "Default")
      (node (ref "U1") (pin "2") (pinfunction "PE3/TRACED0/FSMC_A19_2") (pintype "passive+no_connect"))
    )
    (net (code "96") (name "unconnected-(U1-VCAP-Pad73)") (class "Default")
      (node (ref "U1") (pin "73") (pinfunction "VCAP_73") (pintype "passive+no_connect"))
    )
    (net (code "97") (name "unconnected-(U2-NC-Pad8)") (class "Default")
      (node (ref "U2") (pin "8") (pinfunction "NC_8") (pintype "passive"))
    )
    (net (code "98") (name "unconnected-(U2-NC-Pad9)") (class "Default")
      (node (ref "U2") (pin "9") (pinfunction "NC_9") (pintype "passive"))
    )
  )
)
